# Sheet2.net
KiCad netlist of a schematic drawn in Altium Designer
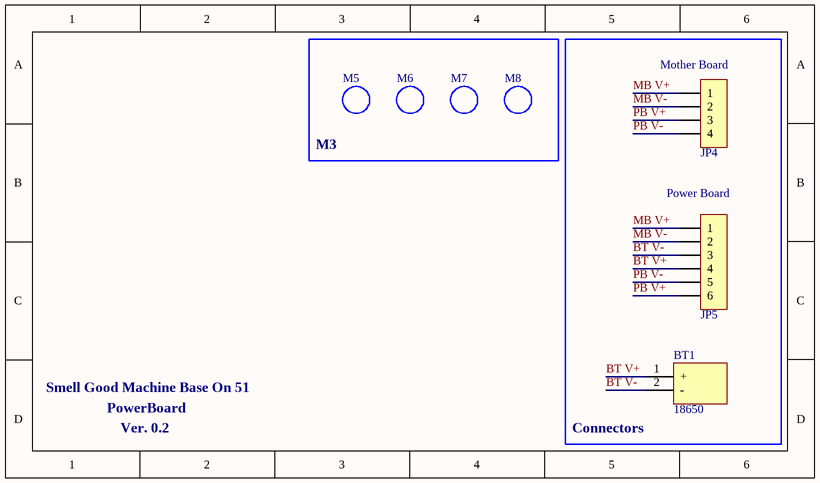
[diagram p0: Sheet2.SchDoc]

(export (version "E")
  (design (tool "Eeschema 10.0.6"))
  (components
    (comp (ref "BT1")
      (value "18650")
      (footprint "18650_battery")
      (description "Battery")
      (libsource (lib "10 - 未分类元器件") (part "18650"))
    )
    (comp (ref "JP4")
      (value "HDR-1X4")
      (footprint "HDR2.54-M-LI-4P")
      (description "4P接插件")
      (libsource (lib "17 - 接插件-脚距2.54mm (100mil) ") (part "Header 4"))
    )
    (comp (ref "JP5")
      (value "HDR-1X6")
      (footprint "HDR2.54-M-LI-6P")
      (description "6P接插件")
      (libsource (lib "17 - 接插件-脚距2.54mm (100mil) ") (part "Header 6"))
    )
    (comp (ref "M5")
      (value "M3")
      (footprint "M3x20_N")
      (description "铜柱孔")
      (libsource (lib "10 - 未分类元器件") (part "M3"))
    )
    (comp (ref "M6")
      (value "M3")
      (footprint "M3x20_N")
      (description "铜柱孔")
      (libsource (lib "10 - 未分类元器件") (part "M3"))
    )
    (comp (ref "M7")
      (value "M3")
      (footprint "M3x20_N")
      (description "铜柱孔")
      (libsource (lib "10 - 未分类元器件") (part "M3"))
    )
    (comp (ref "M8")
      (value "M3")
      (footprint "M3x20_N")
      (description "铜柱孔")
      (libsource (lib "10 - 未分类元器件") (part "M3"))
    )
  )
  (nets
    (net (code "1") (name "/BT V+") (class "Default")
      (node (ref "BT1") (pin "1") (pinfunction "+_1") (pintype "passive"))
      (node (ref "JP5") (pin "4") (pinfunction "4_4") (pintype "passive"))
    )
    (net (code "2") (name "/BT V-") (class "Default")
      (node (ref "BT1") (pin "2") (pinfunction "-_2") (pintype "passive"))
      (node (ref "JP5") (pin "3") (pinfunction "3_3") (pintype "passive"))
    )
    (net (code "3") (name "/MB V+") (class "Default")
      (node (ref "JP4") (pin "1") (pinfunction "1_1") (pintype "passive"))
      (node (ref "JP5") (pin "1") (pinfunction "1_1") (pintype "passive"))
    )
    (net (code "4") (name "/MB V-") (class "Default")
      (node (ref "JP4") (pin "2") (pinfunction "2_2") (pintype "passive"))
      (node (ref "JP5") (pin "2") (pinfunction "2_2") (pintype "passive"))
    )
    (net (code "5") (name "/PB V+") (class "Default")
      (node (ref "JP4") (pin "3") (pinfunction "3_3") (pintype "passive"))
      (node (ref "JP5") (pin "6") (pinfunction "6_6") (pintype "passive"))
    )
    (net (code "6") (name "/PB V-") (class "Default")
      (node (ref "JP4") (pin "4") (pinfunction "4_4") (pintype "passive"))
      (node (ref "JP5") (pin "5") (pinfunction "5_5") (pintype "passive"))
    )
  )
)
